# Thermokoppel.net
KiCad netlist of a schematic drawn in Altium Designer
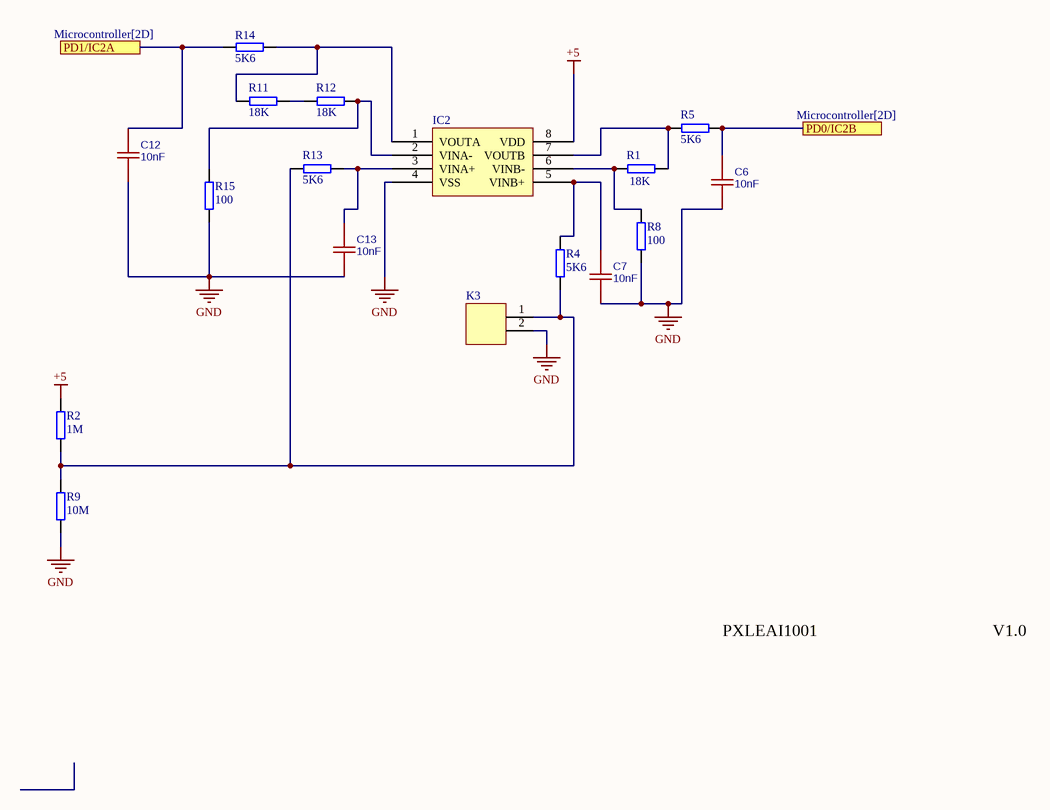
[diagram p0: Thermokoppel.SchDoc]

(export (version "E")
  (design (tool "Eeschema 10.0.6"))
  (components
    (comp (ref "C6")
      (value "10nF")
      (footprint "C6,7,12,13 10nF")
      (fields
        (field (name "BOM_SUPPLIER PART") "C376921")
        (field (name "BOM_MANUFACTURER PART") "TCC0805X7R103M500DT")
        (field (name "CONTRIBUTOR") "LCSC")
      )
      (libsource (lib "SoldeerStation") (part "C6,7,12,13 10nF"))
    )
    (comp (ref "C7")
      (value "10nF")
      (footprint "C6,7,12,13 10nF")
      (fields
        (field (name "BOM_SUPPLIER PART") "C376921")
        (field (name "BOM_MANUFACTURER PART") "TCC0805X7R103M500DT")
        (field (name "CONTRIBUTOR") "LCSC")
      )
      (libsource (lib "SoldeerStation") (part "C6,7,12,13 10nF"))
    )
    (comp (ref "C12")
      (value "10nF")
      (footprint "C6,7,12,13 10nF")
      (fields
        (field (name "BOM_SUPPLIER PART") "C376921")
        (field (name "BOM_MANUFACTURER PART") "TCC0805X7R103M500DT")
        (field (name "CONTRIBUTOR") "LCSC")
      )
      (libsource (lib "SoldeerStation") (part "C6,7,12,13 10nF"))
    )
    (comp (ref "C13")
      (value "10nF")
      (footprint "C6,7,12,13 10nF")
      (fields
        (field (name "BOM_SUPPLIER PART") "C376921")
        (field (name "BOM_MANUFACTURER PART") "TCC0805X7R103M500DT")
        (field (name "CONTRIBUTOR") "LCSC")
      )
      (libsource (lib "SoldeerStation") (part "C6,7,12,13 10nF"))
    )
    (comp (ref "IC2")
      (value "~")
      (footprint "IC2 opamps")
      (description "IC2 dual opamps")
      (libsource (lib "SoldeerStation") (part "IC2 dual opamps"))
    )
    (comp (ref "K3")
      (value "~")
      (footprint "Terminal_2")
      (libsource (lib "SoldeerStation") (part "K Terminal_2"))
    )
    (comp (ref "R1")
      (value "18K")
      (footprint "RESC2013X50X30ML20T20")
      (fields (field (name "MANUFACTURER") "Vishay Dale") (field (name "PART NUMBER") "CRCW08050000Z0EA"))
      (libsource (lib "SoldeerStation") (part "R Resistor"))
    )
    (comp (ref "R2")
      (value "1M")
      (footprint "RESC2013X50X30ML20T20")
      (fields (field (name "MANUFACTURER") "Vishay Dale") (field (name "PART NUMBER") "CRCW08050000Z0EA"))
      (libsource (lib "SoldeerStation") (part "R Resistor"))
    )
    (comp (ref "R4")
      (value "5K6")
      (footprint "RESC2013X50X30ML20T20")
      (fields (field (name "MANUFACTURER") "Vishay Dale") (field (name "PART NUMBER") "CRCW08050000Z0EA"))
      (libsource (lib "") (part "R Resistor_1"))
    )
    (comp (ref "R5")
      (value "5K6")
      (footprint "RESC2013X50X30ML20T20")
      (fields (field (name "MANUFACTURER") "Vishay Dale") (field (name "PART NUMBER") "CRCW08050000Z0EA"))
      (libsource (lib "") (part "R Resistor_1"))
    )
    (comp (ref "R8")
      (value "100")
      (footprint "RESC2013X50X30ML20T20")
      (fields (field (name "MANUFACTURER") "Vishay Dale") (field (name "PART NUMBER") "CRCW08050000Z0EA"))
      (libsource (lib "SoldeerStation") (part "R Resistor"))
    )
    (comp (ref "R9")
      (value "10M")
      (footprint "RESC2013X50X30ML20T20")
      (fields (field (name "MANUFACTURER") "Vishay Dale") (field (name "PART NUMBER") "CRCW08050000Z0EA"))
      (libsource (lib "SoldeerStation") (part "R Resistor"))
    )
    (comp (ref "R11")
      (value "18K")
      (footprint "RESC2013X50X30ML20T20")
      (fields (field (name "MANUFACTURER") "Vishay Dale") (field (name "PART NUMBER") "CRCW08050000Z0EA"))
      (libsource (lib "SoldeerStation") (part "R Resistor"))
    )
    (comp (ref "R12")
      (value "18K")
      (footprint "RESC2013X50X30ML20T20")
      (fields (field (name "MANUFACTURER") "Vishay Dale") (field (name "PART NUMBER") "CRCW08050000Z0EA"))
      (libsource (lib "SoldeerStation") (part "R Resistor"))
    )
    (comp (ref "R13")
      (value "5K6")
      (footprint "RESC2013X50X30ML20T20")
      (fields (field (name "MANUFACTURER") "Vishay Dale") (field (name "PART NUMBER") "CRCW08050000Z0EA"))
      (libsource (lib "") (part "R Resistor_1"))
    )
    (comp (ref "R14")
      (value "5K6")
      (footprint "RESC2013X50X30ML20T20")
      (fields (field (name "MANUFACTURER") "Vishay Dale") (field (name "PART NUMBER") "CRCW08050000Z0EA"))
      (libsource (lib "SoldeerStation") (part "R Resistor"))
    )
    (comp (ref "R15")
      (value "100")
      (footprint "RESC2013X50X30ML20T20")
      (fields (field (name "MANUFACTURER") "Vishay Dale") (field (name "PART NUMBER") "CRCW08050000Z0EA"))
      (libsource (lib "SoldeerStation") (part "R Resistor"))
    )
  )
  (nets
    (net (code "1") (name "+5") (class "Default")
      (node (ref "IC2") (pin "8") (pinfunction "VDD_8") (pintype "passive"))
      (node (ref "R2") (pin "2") (pinfunction "2_2") (pintype "passive"))
    )
    (net (code "2") (name "/PD0{slash}IC2B") (class "Default")
      (node (ref "C6") (pin "2") (pinfunction "2_2") (pintype "passive"))
      (node (ref "R5") (pin "1") (pinfunction "1_1") (pintype "passive"))
    )
    (net (code "3") (name "/PD1{slash}IC2A") (class "Default")
      (node (ref "C12") (pin "2") (pinfunction "2_2") (pintype "passive"))
      (node (ref "R14") (pin "1") (pinfunction "1_1") (pintype "passive"))
    )
    (net (code "4") (name "GND") (class "Default")
      (node (ref "C12") (pin "1") (pinfunction "1_1") (pintype "passive"))
      (node (ref "C13") (pin "1") (pinfunction "1_1") (pintype "passive"))
      (node (ref "C6") (pin "1") (pinfunction "1_1") (pintype "passive"))
      (node (ref "C7") (pin "1") (pinfunction "1_1") (pintype "passive"))
      (node (ref "IC2") (pin "4") (pinfunction "VSS_4") (pintype "passive"))
      (node (ref "K3") (pin "2") (pintype "passive"))
      (node (ref "R15") (pin "1") (pinfunction "1_1") (pintype "passive"))
      (node (ref "R8") (pin "1") (pinfunction "1_1") (pintype "passive"))
      (node (ref "R9") (pin "1") (pinfunction "1_1") (pintype "passive"))
    )
    (net (code "5") (name "Net-(IC2-VINA+)") (class "Default")
      (node (ref "C13") (pin "2") (pinfunction "2_2") (pintype "passive"))
      (node (ref "IC2") (pin "3") (pinfunction "VINA+_3") (pintype "passive"))
      (node (ref "R13") (pin "2") (pinfunction "2_2") (pintype "passive"))
    )
    (net (code "6") (name "Net-(IC2-VINA-)") (class "Default")
      (node (ref "IC2") (pin "2") (pinfunction "VINA-_2") (pintype "passive"))
      (node (ref "R12") (pin "2") (pinfunction "2_2") (pintype "passive"))
      (node (ref "R15") (pin "2") (pinfunction "2_2") (pintype "passive"))
    )
    (net (code "7") (name "Net-(IC2-VINB+)") (class "Default")
      (node (ref "C7") (pin "2") (pinfunction "2_2") (pintype "passive"))
      (node (ref "IC2") (pin "5") (pinfunction "VINB+_5") (pintype "passive"))
      (node (ref "R4") (pin "1") (pinfunction "1_1") (pintype "passive"))
    )
    (net (code "8") (name "Net-(IC2-VINB-)") (class "Default")
      (node (ref "IC2") (pin "6") (pinfunction "VINB-_6") (pintype "passive"))
      (node (ref "R1") (pin "1") (pinfunction "1_1") (pintype "passive"))
      (node (ref "R8") (pin "2") (pinfunction "2_2") (pintype "passive"))
    )
    (net (code "9") (name "Net-(IC2-VOUTA)") (class "Default")
      (node (ref "IC2") (pin "1") (pinfunction "VOUTA_1") (pintype "passive"))
      (node (ref "R11") (pin "2") (pinfunction "2_2") (pintype "passive"))
      (node (ref "R14") (pin "2") (pinfunction "2_2") (pintype "passive"))
    )
    (net (code "10") (name "Net-(IC2-VOUTB)") (class "Default")
      (node (ref "IC2") (pin "7") (pinfunction "VOUTB_7") (pintype "passive"))
      (node (ref "R1") (pin "2") (pinfunction "2_2") (pintype "passive"))
      (node (ref "R5") (pin "2") (pinfunction "2_2") (pintype "passive"))
    )
    (net (code "11") (name "Net-(K3-Pad1)") (class "Default")
      (node (ref "K3") (pin "1") (pintype "passive"))
      (node (ref "R13") (pin "1") (pinfunction "1_1") (pintype "passive"))
      (node (ref "R2") (pin "1") (pinfunction "1_1") (pintype "passive"))
      (node (ref "R4") (pin "2") (pinfunction "2_2") (pintype "passive"))
      (node (ref "R9") (pin "2") (pinfunction "2_2") (pintype "passive"))
    )
    (net (code "12") (name "Net-(R11-Pad1)") (class "Default")
      (node (ref "R11") (pin "1") (pinfunction "1_1") (pintype "passive"))
      (node (ref "R12") (pin "1") (pinfunction "1_1") (pintype "passive"))
    )
  )
)
